# med_filter.net
KiCad netlist of a schematic drawn in Altium Designer
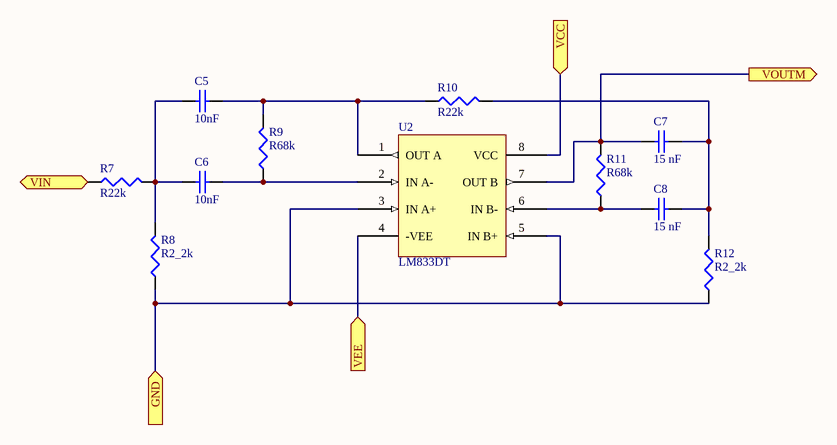
[diagram p0: med_filter.SchDoc]

(export (version "E")
  (design (tool "Eeschema 10.0.6"))
  (components
    (comp (ref "C5")
      (value "10nF")
      (footprint "C0603")
      (description "10 nF Surface Mount Capacitor")
      (fields
        (field (name "MANUFACTURER") "Murata Electronics North America")
        (field (name "MANUFACTURER PART NUMBER") "GRM188R70J103KA01D")
      )
      (libsource (lib "Capstone Libraries") (part "C10nF"))
    )
    (comp (ref "C6")
      (value "10nF")
      (footprint "C0603")
      (description "10 nF Surface Mount Capacitor")
      (fields
        (field (name "MANUFACTURER") "Murata Electronics North America")
        (field (name "MANUFACTURER PART NUMBER") "GRM188R70J103KA01D")
      )
      (libsource (lib "Capstone Libraries") (part "C10nF"))
    )
    (comp (ref "C7")
      (value "15 nF")
      (footprint "C0603")
      (description "15 nF Surface Mount Capacitor")
      (fields
        (field (name "MANUFACTURER") "Murata Electronics North America")
        (field (name "MANUFACTURER PART NUMBER") "GRM188R71H153KA01D")
      )
      (libsource (lib "Capstone Libraries") (part "C15nF"))
    )
    (comp (ref "C8")
      (value "15 nF")
      (footprint "C0603")
      (description "15 nF Surface Mount Capacitor")
      (fields
        (field (name "MANUFACTURER") "Murata Electronics North America")
        (field (name "MANUFACTURER PART NUMBER") "GRM188R71H153KA01D")
      )
      (libsource (lib "Capstone Libraries") (part "C15nF"))
    )
    (comp (ref "R7")
      (value "R22k")
      (footprint "R0603")
      (description "22k Ohms Surface Mount Resistor")
      (fields
        (field (name "MANUFACTURER") "Yageo")
        (field (name "MANUFACTURER PART NUMBER") "RC0603FR-0722KL")
      )
      (libsource (lib "Capstone Libraries") (part "R22k"))
    )
    (comp (ref "R8")
      (value "R2_2k")
      (footprint "R0603")
      (description "2.2k Ohms Surface Mount Resistor")
      (fields
        (field (name "MANUFACTURER") "Yageo")
        (field (name "MANUFACTURER PART NUMBER") "RC0603FR-072K2L")
      )
      (libsource (lib "Capstone Libraries") (part "R2_2k"))
    )
    (comp (ref "R9")
      (value "R68k")
      (footprint "R0603")
      (description "68k Ohms Surface Mount Resistor")
      (fields
        (field (name "MANUFACTURER") "Panasonic Electronic Components")
        (field (name "MANUFACTURER PART NUMBER") "ERJ-3EKF6802V")
      )
      (libsource (lib "Capstone Libraries") (part "R68k"))
    )
    (comp (ref "R10")
      (value "R22k")
      (footprint "R0603")
      (description "22k Ohms Surface Mount Resistor")
      (fields
        (field (name "MANUFACTURER") "Yageo")
        (field (name "MANUFACTURER PART NUMBER") "RC0603FR-0722KL")
      )
      (libsource (lib "Capstone Libraries") (part "R22k"))
    )
    (comp (ref "R11")
      (value "R68k")
      (footprint "R0603")
      (description "68k Ohms Surface Mount Resistor")
      (fields
        (field (name "MANUFACTURER") "Panasonic Electronic Components")
        (field (name "MANUFACTURER PART NUMBER") "ERJ-3EKF6802V")
      )
      (libsource (lib "Capstone Libraries") (part "R68k"))
    )
    (comp (ref "R12")
      (value "R2_2k")
      (footprint "R0603")
      (description "2.2k Ohms Surface Mount Resistor")
      (fields
        (field (name "MANUFACTURER") "Yageo")
        (field (name "MANUFACTURER PART NUMBER") "RC0603FR-072K2L")
      )
      (libsource (lib "Capstone Libraries") (part "R2_2k"))
    )
    (comp (ref "U2")
      (value "LM833DT")
      (footprint "soic8")
      (description "IC Dual Audio Amplifier")
      (fields (field (name "MANUFACTURER") "STMicroelectronics"))
      (libsource (lib "Capstone Libraries") (part "LM833DT"))
    )
  )
  (nets
    (net (code "1") (name "/GND") (class "Default")
      (node (ref "R12") (pin "1") (pinfunction "1_1") (pintype "passive"))
      (node (ref "R8") (pin "1") (pinfunction "1_1") (pintype "passive"))
      (node (ref "U2") (pin "3") (pinfunction "IN_A+_3") (pintype "input"))
      (node (ref "U2") (pin "5") (pinfunction "IN_B+_5") (pintype "input"))
    )
    (net (code "2") (name "/VCC") (class "Default")
      (node (ref "U2") (pin "8") (pinfunction "VCC_8") (pintype "passive"))
    )
    (net (code "3") (name "/VEE") (class "Default")
      (node (ref "U2") (pin "4") (pinfunction "-VEE_4") (pintype "passive"))
    )
    (net (code "4") (name "/VIN") (class "Default")
      (node (ref "R7") (pin "1") (pinfunction "1_1") (pintype "passive"))
    )
    (net (code "5") (name "/VOUTM") (class "Default")
      (node (ref "C7") (pin "1") (pinfunction "1_1") (pintype "passive"))
      (node (ref "R11") (pin "2") (pinfunction "2_2") (pintype "passive"))
      (node (ref "U2") (pin "7") (pinfunction "OUT_B_7") (pintype "output"))
    )
    (net (code "6") (name "Net-(C5-Pad1)") (class "Default")
      (node (ref "C5") (pin "1") (pinfunction "1_1") (pintype "passive"))
      (node (ref "C6") (pin "1") (pinfunction "1_1") (pintype "passive"))
      (node (ref "R7") (pin "2") (pinfunction "2_2") (pintype "passive"))
      (node (ref "R8") (pin "2") (pinfunction "2_2") (pintype "passive"))
    )
    (net (code "7") (name "Net-(C7-Pad2)") (class "Default")
      (node (ref "C7") (pin "2") (pinfunction "2_2") (pintype "passive"))
      (node (ref "C8") (pin "2") (pinfunction "2_2") (pintype "passive"))
      (node (ref "R10") (pin "2") (pinfunction "2_2") (pintype "passive"))
      (node (ref "R12") (pin "2") (pinfunction "2_2") (pintype "passive"))
    )
    (net (code "8") (name "Net-(U2-IN_A-)") (class "Default")
      (node (ref "C6") (pin "2") (pinfunction "2_2") (pintype "passive"))
      (node (ref "R9") (pin "1") (pinfunction "1_1") (pintype "passive"))
      (node (ref "U2") (pin "2") (pinfunction "IN_A-_2") (pintype "input"))
    )
    (net (code "9") (name "Net-(U2-IN_B-)") (class "Default")
      (node (ref "C8") (pin "1") (pinfunction "1_1") (pintype "passive"))
      (node (ref "R11") (pin "1") (pinfunction "1_1") (pintype "passive"))
      (node (ref "U2") (pin "6") (pinfunction "IN_B-_6") (pintype "input"))
    )
    (net (code "10") (name "Net-(U2-OUT_A)") (class "Default")
      (node (ref "C5") (pin "2") (pinfunction "2_2") (pintype "passive"))
      (node (ref "R10") (pin "1") (pinfunction "1_1") (pintype "passive"))
      (node (ref "R9") (pin "2") (pinfunction "2_2") (pintype "passive"))
      (node (ref "U2") (pin "1") (pinfunction "OUT_A_1") (pintype "output"))
    )
  )
)
